# umodular_mega_shield_rev01.net
KiCad netlist of a schematic drawn in EAGLE
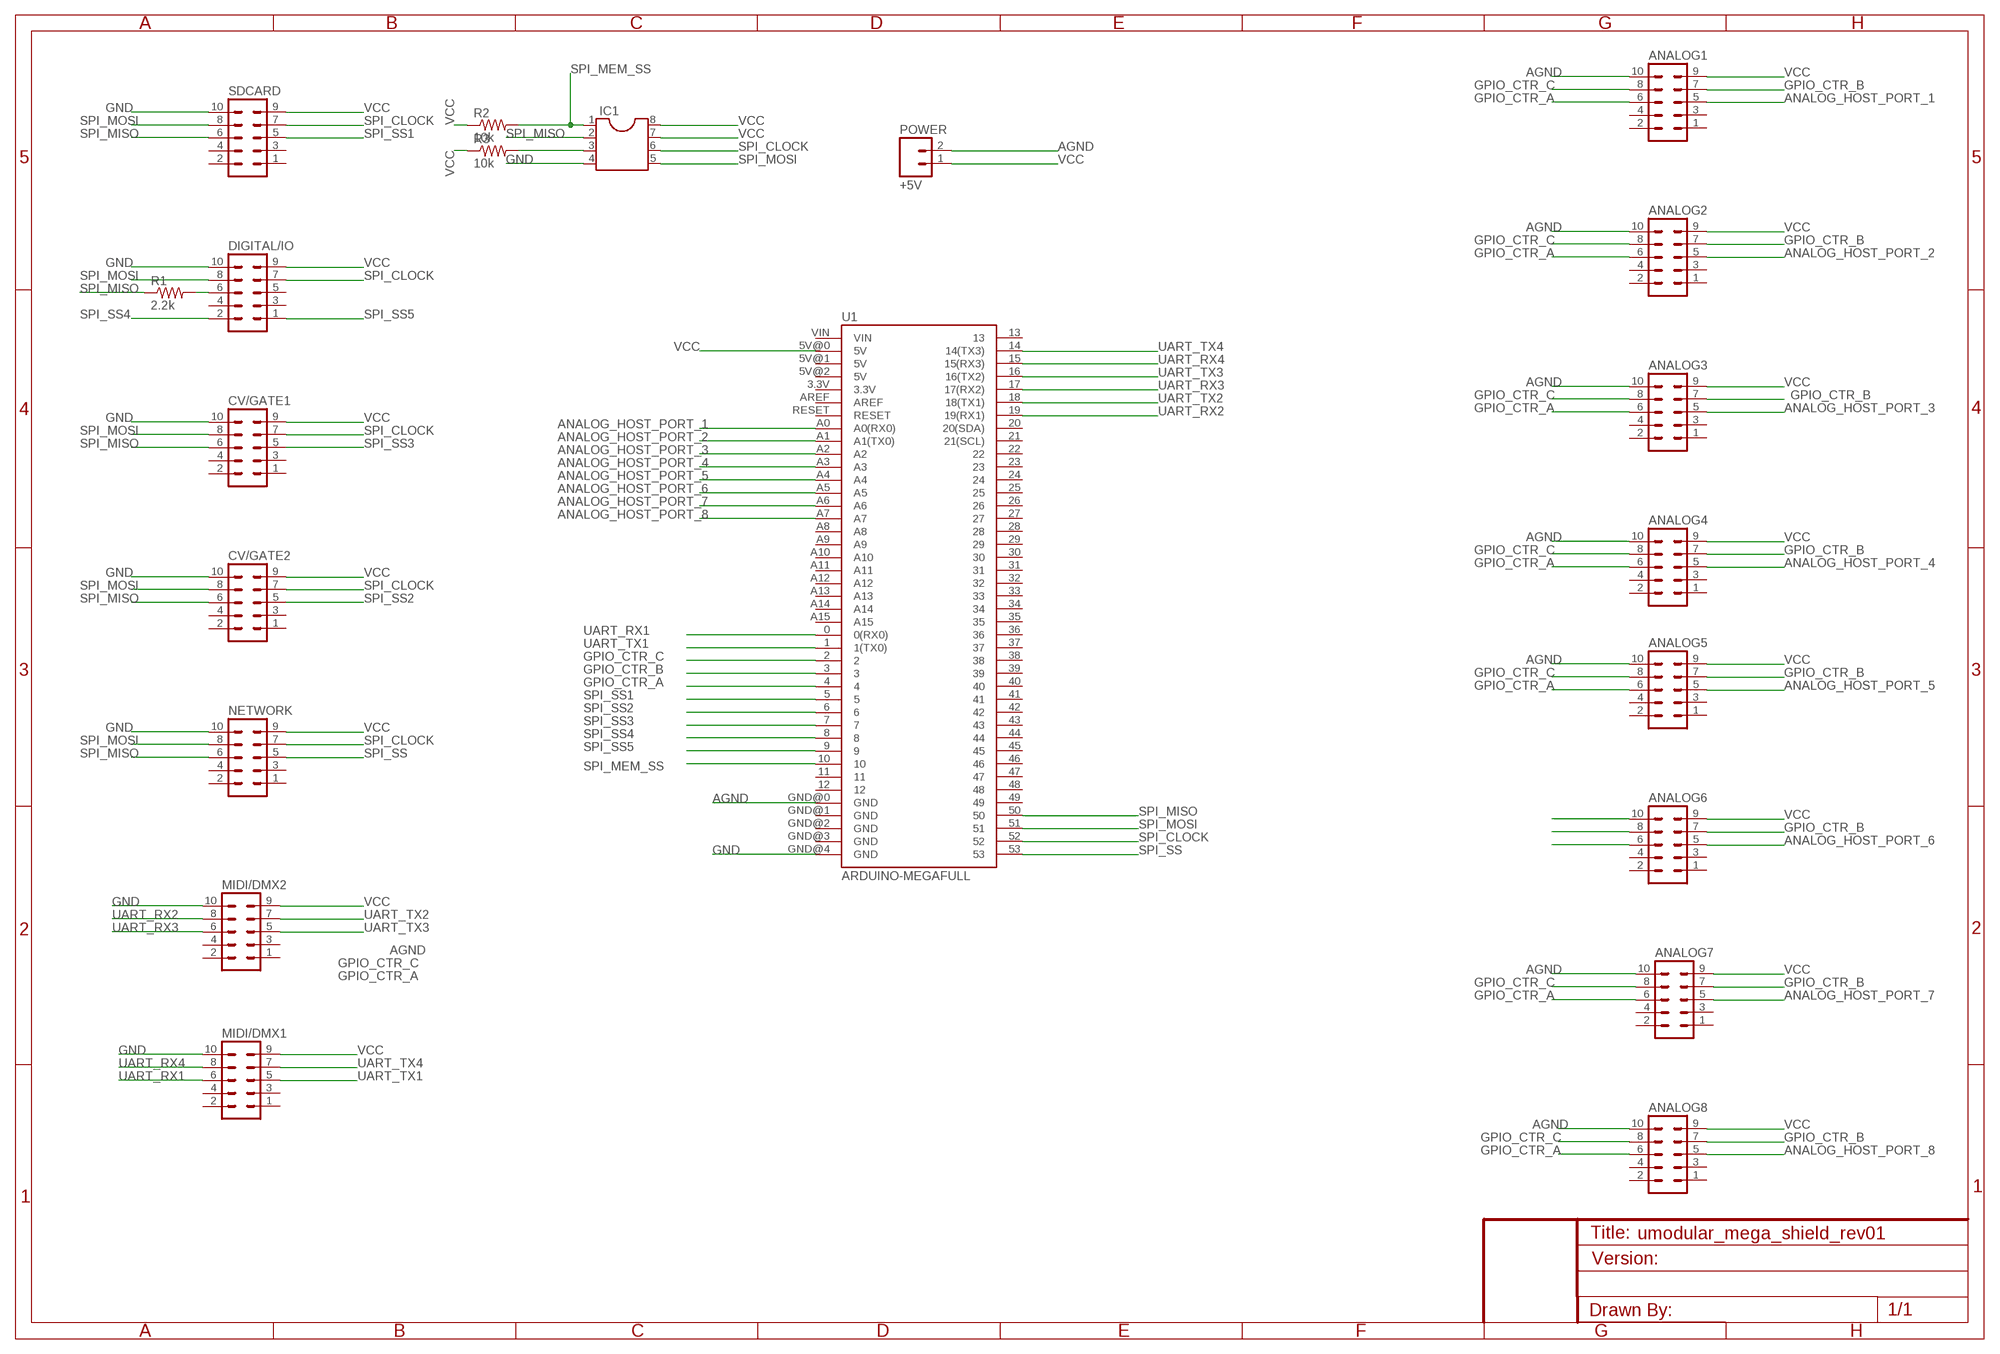
[diagram p0: schematic, sheet 1]

(export (version "E")
  (design (tool "Eeschema 10.0.6"))
  (components
    (comp (ref "ANALOG1")
      (value "MA05-2")
      (footprint "eagle-import:MA05-2")
      (libsource (lib "eagle-import") (part "MA05-2"))
    )
    (comp (ref "ANALOG2")
      (value "MA05-2")
      (footprint "eagle-import:MA05-2")
      (libsource (lib "eagle-import") (part "MA05-2"))
    )
    (comp (ref "ANALOG3")
      (value "MA05-2")
      (footprint "eagle-import:MA05-2")
      (libsource (lib "eagle-import") (part "MA05-2"))
    )
    (comp (ref "ANALOG4")
      (value "MA05-2")
      (footprint "eagle-import:MA05-2")
      (libsource (lib "eagle-import") (part "MA05-2"))
    )
    (comp (ref "ANALOG5")
      (value "MA05-2")
      (footprint "eagle-import:MA05-2")
      (libsource (lib "eagle-import") (part "MA05-2"))
    )
    (comp (ref "ANALOG6")
      (value "MA05-2")
      (footprint "eagle-import:MA05-2")
      (libsource (lib "eagle-import") (part "MA05-2"))
    )
    (comp (ref "ANALOG7")
      (value "MA05-2")
      (footprint "eagle-import:MA05-2")
      (libsource (lib "eagle-import") (part "MA05-2"))
    )
    (comp (ref "ANALOG8")
      (value "MA05-2")
      (footprint "eagle-import:MA05-2")
      (libsource (lib "eagle-import") (part "MA05-2"))
    )
    (comp (ref "CV/GATE1")
      (value "MA05-2")
      (footprint "eagle-import:MA05-2")
      (libsource (lib "eagle-import") (part "MA05-2"))
    )
    (comp (ref "CV/GATE2")
      (value "MA05-2")
      (footprint "eagle-import:MA05-2")
      (libsource (lib "eagle-import") (part "MA05-2"))
    )
    (comp (ref "DIGITAL/IO")
      (value "MA05-2")
      (footprint "eagle-import:MA05-2")
      (libsource (lib "eagle-import") (part "MA05-2"))
    )
    (comp (ref "IC1")
      (value "DIL8")
      (footprint "eagle-import:DIL08")
      (libsource (lib "eagle-import") (part "DIL8"))
    )
    (comp (ref "MIDI/DMX1")
      (value "MA05-2")
      (footprint "eagle-import:MA05-2")
      (libsource (lib "eagle-import") (part "MA05-2"))
    )
    (comp (ref "MIDI/DMX2")
      (value "MA05-2")
      (footprint "eagle-import:MA05-2")
      (libsource (lib "eagle-import") (part "MA05-2"))
    )
    (comp (ref "NETWORK")
      (value "MA05-2")
      (footprint "eagle-import:MA05-2")
      (libsource (lib "eagle-import") (part "MA05-2"))
    )
    (comp (ref "POWER")
      (value "+5V")
      (footprint "eagle-import:1X02_LOCK_LONGPADS")
      (libsource (lib "eagle-import") (part "M02LOCK_LONGPADS"))
    )
    (comp (ref "R1")
      (value "2.2k")
      (footprint "eagle-import:0204_7")
      (libsource (lib "eagle-import") (part "R-US_0204/7"))
    )
    (comp (ref "R2")
      (value "10k")
      (footprint "eagle-import:0204_7")
      (libsource (lib "eagle-import") (part "R-US_0204/7"))
    )
    (comp (ref "R3")
      (value "10k")
      (footprint "eagle-import:0204_7")
      (libsource (lib "eagle-import") (part "R-US_0204/7"))
    )
    (comp (ref "SDCARD")
      (value "MA05-2")
      (footprint "eagle-import:MA05-2")
      (libsource (lib "eagle-import") (part "MA05-2"))
    )
    (comp (ref "U1")
      (value "ARDUINO-MEGAFULL")
      (footprint "eagle-import:ARDUINO_MEGA")
      (libsource (lib "eagle-import") (part "ARDUINO-MEGAFULL"))
    )
  )
  (nets
    (net (code "1") (name "/AGND") (class "Default")
      (node (ref "ANALOG1") (pin "10") (pinfunction "10_10") (pintype "passive"))
      (node (ref "ANALOG2") (pin "10") (pinfunction "10_10") (pintype "passive"))
      (node (ref "ANALOG3") (pin "10") (pinfunction "10_10") (pintype "passive"))
      (node (ref "ANALOG4") (pin "10") (pinfunction "10_10") (pintype "passive"))
      (node (ref "ANALOG5") (pin "10") (pinfunction "10_10") (pintype "passive"))
      (node (ref "ANALOG6") (pin "10") (pinfunction "10_10") (pintype "passive"))
      (node (ref "ANALOG7") (pin "10") (pinfunction "10_10") (pintype "passive"))
      (node (ref "ANALOG8") (pin "10") (pinfunction "10_10") (pintype "passive"))
      (node (ref "POWER") (pin "2") (pinfunction "2_2") (pintype "passive"))
      (node (ref "U1") (pin "GND@0") (pinfunction "GND_GND@0") (pintype "bidirectional"))
    )
    (net (code "2") (name "/ANALOG_HOST_PORT_1") (class "Default")
      (node (ref "ANALOG1") (pin "5") (pinfunction "5_5") (pintype "passive"))
      (node (ref "U1") (pin "A0") (pinfunction "A0(RX0)_A0") (pintype "bidirectional"))
    )
    (net (code "3") (name "/ANALOG_HOST_PORT_2") (class "Default")
      (node (ref "ANALOG2") (pin "5") (pinfunction "5_5") (pintype "passive"))
      (node (ref "U1") (pin "A1") (pinfunction "A1(TX0)_A1") (pintype "bidirectional"))
    )
    (net (code "4") (name "/ANALOG_HOST_PORT_3") (class "Default")
      (node (ref "ANALOG3") (pin "5") (pinfunction "5_5") (pintype "passive"))
      (node (ref "U1") (pin "A2") (pinfunction "A2_A2") (pintype "bidirectional"))
    )
    (net (code "5") (name "/ANALOG_HOST_PORT_4") (class "Default")
      (node (ref "ANALOG4") (pin "5") (pinfunction "5_5") (pintype "passive"))
      (node (ref "U1") (pin "A3") (pinfunction "A3_A3") (pintype "bidirectional"))
    )
    (net (code "6") (name "/ANALOG_HOST_PORT_5") (class "Default")
      (node (ref "ANALOG5") (pin "5") (pinfunction "5_5") (pintype "passive"))
      (node (ref "U1") (pin "A4") (pinfunction "A4_A4") (pintype "bidirectional"))
    )
    (net (code "7") (name "/ANALOG_HOST_PORT_6") (class "Default")
      (node (ref "ANALOG6") (pin "5") (pinfunction "5_5") (pintype "passive"))
      (node (ref "U1") (pin "A5") (pinfunction "A5_A5") (pintype "bidirectional"))
    )
    (net (code "8") (name "/ANALOG_HOST_PORT_7") (class "Default")
      (node (ref "ANALOG7") (pin "5") (pinfunction "5_5") (pintype "passive"))
      (node (ref "U1") (pin "A6") (pinfunction "A6_A6") (pintype "bidirectional"))
    )
    (net (code "9") (name "/ANALOG_HOST_PORT_8") (class "Default")
      (node (ref "ANALOG8") (pin "5") (pinfunction "5_5") (pintype "passive"))
      (node (ref "U1") (pin "A7") (pinfunction "A7_A7") (pintype "bidirectional"))
    )
    (net (code "10") (name "/GND") (class "Default")
      (node (ref "CV/GATE1") (pin "10") (pinfunction "10_10") (pintype "passive"))
      (node (ref "CV/GATE2") (pin "10") (pinfunction "10_10") (pintype "passive"))
      (node (ref "DIGITAL/IO") (pin "10") (pinfunction "10_10") (pintype "passive"))
      (node (ref "IC1") (pin "4") (pinfunction "4_4") (pintype "passive"))
      (node (ref "MIDI/DMX1") (pin "10") (pinfunction "10_10") (pintype "passive"))
      (node (ref "MIDI/DMX2") (pin "10") (pinfunction "10_10") (pintype "passive"))
      (node (ref "NETWORK") (pin "10") (pinfunction "10_10") (pintype "passive"))
      (node (ref "SDCARD") (pin "10") (pinfunction "10_10") (pintype "passive"))
      (node (ref "U1") (pin "GND@4") (pinfunction "GND_GND@4") (pintype "bidirectional"))
    )
    (net (code "11") (name "/GPIO_CTR_A") (class "Default")
      (node (ref "ANALOG1") (pin "6") (pinfunction "6_6") (pintype "passive"))
      (node (ref "ANALOG2") (pin "6") (pinfunction "6_6") (pintype "passive"))
      (node (ref "ANALOG3") (pin "6") (pinfunction "6_6") (pintype "passive"))
      (node (ref "ANALOG4") (pin "6") (pinfunction "6_6") (pintype "passive"))
      (node (ref "ANALOG5") (pin "6") (pinfunction "6_6") (pintype "passive"))
      (node (ref "ANALOG6") (pin "6") (pinfunction "6_6") (pintype "passive"))
      (node (ref "ANALOG7") (pin "6") (pinfunction "6_6") (pintype "passive"))
      (node (ref "ANALOG8") (pin "6") (pinfunction "6_6") (pintype "passive"))
      (node (ref "U1") (pin "4") (pinfunction "4_4") (pintype "bidirectional"))
    )
    (net (code "12") (name "/GPIO_CTR_B") (class "Default")
      (node (ref "ANALOG1") (pin "7") (pinfunction "7_7") (pintype "passive"))
      (node (ref "ANALOG2") (pin "7") (pinfunction "7_7") (pintype "passive"))
      (node (ref "ANALOG3") (pin "7") (pinfunction "7_7") (pintype "passive"))
      (node (ref "ANALOG4") (pin "7") (pinfunction "7_7") (pintype "passive"))
      (node (ref "ANALOG5") (pin "7") (pinfunction "7_7") (pintype "passive"))
      (node (ref "ANALOG6") (pin "7") (pinfunction "7_7") (pintype "passive"))
      (node (ref "ANALOG7") (pin "7") (pinfunction "7_7") (pintype "passive"))
      (node (ref "ANALOG8") (pin "7") (pinfunction "7_7") (pintype "passive"))
      (node (ref "U1") (pin "3") (pinfunction "3_3") (pintype "bidirectional"))
    )
    (net (code "13") (name "/GPIO_CTR_C") (class "Default")
      (node (ref "ANALOG1") (pin "8") (pinfunction "8_8") (pintype "passive"))
      (node (ref "ANALOG2") (pin "8") (pinfunction "8_8") (pintype "passive"))
      (node (ref "ANALOG3") (pin "8") (pinfunction "8_8") (pintype "passive"))
      (node (ref "ANALOG4") (pin "8") (pinfunction "8_8") (pintype "passive"))
      (node (ref "ANALOG5") (pin "8") (pinfunction "8_8") (pintype "passive"))
      (node (ref "ANALOG6") (pin "8") (pinfunction "8_8") (pintype "passive"))
      (node (ref "ANALOG7") (pin "8") (pinfunction "8_8") (pintype "passive"))
      (node (ref "ANALOG8") (pin "8") (pinfunction "8_8") (pintype "passive"))
      (node (ref "U1") (pin "2") (pinfunction "2_2") (pintype "bidirectional"))
    )
    (net (code "14") (name "/SPI_CLOCK") (class "Default")
      (node (ref "CV/GATE1") (pin "7") (pinfunction "7_7") (pintype "passive"))
      (node (ref "CV/GATE2") (pin "7") (pinfunction "7_7") (pintype "passive"))
      (node (ref "DIGITAL/IO") (pin "7") (pinfunction "7_7") (pintype "passive"))
      (node (ref "IC1") (pin "6") (pinfunction "6_6") (pintype "passive"))
      (node (ref "NETWORK") (pin "7") (pinfunction "7_7") (pintype "passive"))
      (node (ref "SDCARD") (pin "7") (pinfunction "7_7") (pintype "passive"))
      (node (ref "U1") (pin "52") (pinfunction "52_52") (pintype "bidirectional"))
    )
    (net (code "15") (name "/SPI_MEM_SS") (class "Default")
      (node (ref "IC1") (pin "1") (pinfunction "1_1") (pintype "passive"))
      (node (ref "R2") (pin "2") (pinfunction "2_2") (pintype "passive"))
      (node (ref "U1") (pin "10") (pinfunction "10_10") (pintype "bidirectional"))
    )
    (net (code "16") (name "/SPI_MISO") (class "Default")
      (node (ref "CV/GATE1") (pin "6") (pinfunction "6_6") (pintype "passive"))
      (node (ref "CV/GATE2") (pin "6") (pinfunction "6_6") (pintype "passive"))
      (node (ref "IC1") (pin "2") (pinfunction "2_2") (pintype "passive"))
      (node (ref "NETWORK") (pin "6") (pinfunction "6_6") (pintype "passive"))
      (node (ref "R1") (pin "1") (pinfunction "1_1") (pintype "passive"))
      (node (ref "SDCARD") (pin "6") (pinfunction "6_6") (pintype "passive"))
      (node (ref "U1") (pin "50") (pinfunction "50_50") (pintype "bidirectional"))
    )
    (net (code "17") (name "/SPI_MOSI") (class "Default")
      (node (ref "CV/GATE1") (pin "8") (pinfunction "8_8") (pintype "passive"))
      (node (ref "CV/GATE2") (pin "8") (pinfunction "8_8") (pintype "passive"))
      (node (ref "DIGITAL/IO") (pin "8") (pinfunction "8_8") (pintype "passive"))
      (node (ref "IC1") (pin "5") (pinfunction "5_5") (pintype "passive"))
      (node (ref "NETWORK") (pin "8") (pinfunction "8_8") (pintype "passive"))
      (node (ref "SDCARD") (pin "8") (pinfunction "8_8") (pintype "passive"))
      (node (ref "U1") (pin "51") (pinfunction "51_51") (pintype "bidirectional"))
    )
    (net (code "18") (name "/SPI_SS") (class "Default")
      (node (ref "NETWORK") (pin "5") (pinfunction "5_5") (pintype "passive"))
      (node (ref "U1") (pin "53") (pinfunction "53_53") (pintype "bidirectional"))
    )
    (net (code "19") (name "/SPI_SS1") (class "Default")
      (node (ref "SDCARD") (pin "5") (pinfunction "5_5") (pintype "passive"))
      (node (ref "U1") (pin "5") (pinfunction "5_5") (pintype "bidirectional"))
    )
    (net (code "20") (name "/SPI_SS2") (class "Default")
      (node (ref "CV/GATE2") (pin "5") (pinfunction "5_5") (pintype "passive"))
      (node (ref "U1") (pin "6") (pinfunction "6_6") (pintype "bidirectional"))
    )
    (net (code "21") (name "/SPI_SS3") (class "Default")
      (node (ref "CV/GATE1") (pin "5") (pinfunction "5_5") (pintype "passive"))
      (node (ref "U1") (pin "7") (pinfunction "7_7") (pintype "bidirectional"))
    )
    (net (code "22") (name "/SPI_SS4") (class "Default")
      (node (ref "DIGITAL/IO") (pin "2") (pinfunction "2_2") (pintype "passive"))
      (node (ref "U1") (pin "8") (pinfunction "8_8") (pintype "bidirectional"))
    )
    (net (code "23") (name "/SPI_SS5") (class "Default")
      (node (ref "DIGITAL/IO") (pin "1") (pinfunction "1_1") (pintype "passive"))
      (node (ref "U1") (pin "9") (pinfunction "9_9") (pintype "bidirectional"))
    )
    (net (code "24") (name "/UART_RX1") (class "Default")
      (node (ref "MIDI/DMX1") (pin "6") (pinfunction "6_6") (pintype "passive"))
      (node (ref "U1") (pin "0") (pinfunction "0(RX0)_0") (pintype "bidirectional"))
    )
    (net (code "25") (name "/UART_RX2") (class "Default")
      (node (ref "MIDI/DMX2") (pin "8") (pinfunction "8_8") (pintype "passive"))
      (node (ref "U1") (pin "19") (pinfunction "19(RX1)_19") (pintype "bidirectional"))
    )
    (net (code "26") (name "/UART_RX3") (class "Default")
      (node (ref "MIDI/DMX2") (pin "6") (pinfunction "6_6") (pintype "passive"))
      (node (ref "U1") (pin "17") (pinfunction "17(RX2)_17") (pintype "bidirectional"))
    )
    (net (code "27") (name "/UART_RX4") (class "Default")
      (node (ref "MIDI/DMX1") (pin "8") (pinfunction "8_8") (pintype "passive"))
      (node (ref "U1") (pin "15") (pinfunction "15(RX3)_15") (pintype "bidirectional"))
    )
    (net (code "28") (name "/UART_TX1") (class "Default")
      (node (ref "MIDI/DMX1") (pin "5") (pinfunction "5_5") (pintype "passive"))
      (node (ref "U1") (pin "1") (pinfunction "1(TX0)_1") (pintype "bidirectional"))
    )
    (net (code "29") (name "/UART_TX2") (class "Default")
      (node (ref "MIDI/DMX2") (pin "7") (pinfunction "7_7") (pintype "passive"))
      (node (ref "U1") (pin "18") (pinfunction "18(TX1)_18") (pintype "bidirectional"))
    )
    (net (code "30") (name "/UART_TX3") (class "Default")
      (node (ref "MIDI/DMX2") (pin "5") (pinfunction "5_5") (pintype "passive"))
      (node (ref "U1") (pin "16") (pinfunction "16(TX2)_16") (pintype "bidirectional"))
    )
    (net (code "31") (name "/UART_TX4") (class "Default")
      (node (ref "MIDI/DMX1") (pin "7") (pinfunction "7_7") (pintype "passive"))
      (node (ref "U1") (pin "14") (pinfunction "14(TX3)_14") (pintype "bidirectional"))
    )
    (net (code "32") (name "/VCC") (class "Default")
      (node (ref "ANALOG1") (pin "9") (pinfunction "9_9") (pintype "passive"))
      (node (ref "ANALOG2") (pin "9") (pinfunction "9_9") (pintype "passive"))
      (node (ref "ANALOG3") (pin "9") (pinfunction "9_9") (pintype "passive"))
      (node (ref "ANALOG4") (pin "9") (pinfunction "9_9") (pintype "passive"))
      (node (ref "ANALOG5") (pin "9") (pinfunction "9_9") (pintype "passive"))
      (node (ref "ANALOG6") (pin "9") (pinfunction "9_9") (pintype "passive"))
      (node (ref "ANALOG7") (pin "9") (pinfunction "9_9") (pintype "passive"))
      (node (ref "ANALOG8") (pin "9") (pinfunction "9_9") (pintype "passive"))
      (node (ref "CV/GATE1") (pin "9") (pinfunction "9_9") (pintype "passive"))
      (node (ref "CV/GATE2") (pin "9") (pinfunction "9_9") (pintype "passive"))
      (node (ref "DIGITAL/IO") (pin "9") (pinfunction "9_9") (pintype "passive"))
      (node (ref "IC1") (pin "7") (pinfunction "7_7") (pintype "passive"))
      (node (ref "IC1") (pin "8") (pinfunction "8_8") (pintype "passive"))
      (node (ref "MIDI/DMX1") (pin "9") (pinfunction "9_9") (pintype "passive"))
      (node (ref "MIDI/DMX2") (pin "9") (pinfunction "9_9") (pintype "passive"))
      (node (ref "NETWORK") (pin "9") (pinfunction "9_9") (pintype "passive"))
      (node (ref "POWER") (pin "1") (pinfunction "1_1") (pintype "passive"))
      (node (ref "R2") (pin "1") (pinfunction "1_1") (pintype "passive"))
      (node (ref "R3") (pin "1") (pinfunction "1_1") (pintype "passive"))
      (node (ref "SDCARD") (pin "9") (pinfunction "9_9") (pintype "passive"))
      (node (ref "U1") (pin "5V@0") (pinfunction "5V_5V@0") (pintype "bidirectional"))
    )
    (net (code "33") (name "Net-(DIGITAL/IO-Pad6)") (class "Default")
      (node (ref "DIGITAL/IO") (pin "6") (pinfunction "6_6") (pintype "passive"))
      (node (ref "R1") (pin "2") (pinfunction "2_2") (pintype "passive"))
    )
    (net (code "34") (name "Net-(IC1-Pad3)") (class "Default")
      (node (ref "IC1") (pin "3") (pinfunction "3_3") (pintype "passive"))
      (node (ref "R3") (pin "2") (pinfunction "2_2") (pintype "passive"))
    )
    (net (code "35") (name "unconnected-(ANALOG1-Pad1)") (class "Default")
      (node (ref "ANALOG1") (pin "1") (pinfunction "1_1") (pintype "passive"))
    )
    (net (code "36") (name "unconnected-(ANALOG1-Pad2)") (class "Default")
      (node (ref "ANALOG1") (pin "2") (pinfunction "2_2") (pintype "passive"))
    )
    (net (code "37") (name "unconnected-(ANALOG1-Pad3)") (class "Default")
      (node (ref "ANALOG1") (pin "3") (pinfunction "3_3") (pintype "passive"))
    )
    (net (code "38") (name "unconnected-(ANALOG1-Pad4)") (class "Default")
      (node (ref "ANALOG1") (pin "4") (pinfunction "4_4") (pintype "passive"))
    )
    (net (code "39") (name "unconnected-(ANALOG2-Pad1)") (class "Default")
      (node (ref "ANALOG2") (pin "1") (pinfunction "1_1") (pintype "passive"))
    )
    (net (code "40") (name "unconnected-(ANALOG2-Pad2)") (class "Default")
      (node (ref "ANALOG2") (pin "2") (pinfunction "2_2") (pintype "passive"))
    )
    (net (code "41") (name "unconnected-(ANALOG2-Pad3)") (class "Default")
      (node (ref "ANALOG2") (pin "3") (pinfunction "3_3") (pintype "passive"))
    )
    (net (code "42") (name "unconnected-(ANALOG2-Pad4)") (class "Default")
      (node (ref "ANALOG2") (pin "4") (pinfunction "4_4") (pintype "passive"))
    )
    (net (code "43") (name "unconnected-(ANALOG3-Pad1)") (class "Default")
      (node (ref "ANALOG3") (pin "1") (pinfunction "1_1") (pintype "passive"))
    )
    (net (code "44") (name "unconnected-(ANALOG3-Pad2)") (class "Default")
      (node (ref "ANALOG3") (pin "2") (pinfunction "2_2") (pintype "passive"))
    )
    (net (code "45") (name "unconnected-(ANALOG3-Pad3)") (class "Default")
      (node (ref "ANALOG3") (pin "3") (pinfunction "3_3") (pintype "passive"))
    )
    (net (code "46") (name "unconnected-(ANALOG3-Pad4)") (class "Default")
      (node (ref "ANALOG3") (pin "4") (pinfunction "4_4") (pintype "passive"))
    )
    (net (code "47") (name "unconnected-(ANALOG4-Pad1)") (class "Default")
      (node (ref "ANALOG4") (pin "1") (pinfunction "1_1") (pintype "passive"))
    )
    (net (code "48") (name "unconnected-(ANALOG4-Pad2)") (class "Default")
      (node (ref "ANALOG4") (pin "2") (pinfunction "2_2") (pintype "passive"))
    )
    (net (code "49") (name "unconnected-(ANALOG4-Pad3)") (class "Default")
      (node (ref "ANALOG4") (pin "3") (pinfunction "3_3") (pintype "passive"))
    )
    (net (code "50") (name "unconnected-(ANALOG4-Pad4)") (class "Default")
      (node (ref "ANALOG4") (pin "4") (pinfunction "4_4") (pintype "passive"))
    )
    (net (code "51") (name "unconnected-(ANALOG5-Pad1)") (class "Default")
      (node (ref "ANALOG5") (pin "1") (pinfunction "1_1") (pintype "passive"))
    )
    (net (code "52") (name "unconnected-(ANALOG5-Pad2)") (class "Default")
      (node (ref "ANALOG5") (pin "2") (pinfunction "2_2") (pintype "passive"))
    )
    (net (code "53") (name "unconnected-(ANALOG5-Pad3)") (class "Default")
      (node (ref "ANALOG5") (pin "3") (pinfunction "3_3") (pintype "passive"))
    )
    (net (code "54") (name "unconnected-(ANALOG5-Pad4)") (class "Default")
      (node (ref "ANALOG5") (pin "4") (pinfunction "4_4") (pintype "passive"))
    )
    (net (code "55") (name "unconnected-(ANALOG6-Pad1)") (class "Default")
      (node (ref "ANALOG6") (pin "1") (pinfunction "1_1") (pintype "passive"))
    )
    (net (code "56") (name "unconnected-(ANALOG6-Pad2)") (class "Default")
      (node (ref "ANALOG6") (pin "2") (pinfunction "2_2") (pintype "passive"))
    )
    (net (code "57") (name "unconnected-(ANALOG6-Pad3)") (class "Default")
      (node (ref "ANALOG6") (pin "3") (pinfunction "3_3") (pintype "passive"))
    )
    (net (code "58") (name "unconnected-(ANALOG6-Pad4)") (class "Default")
      (node (ref "ANALOG6") (pin "4") (pinfunction "4_4") (pintype "passive"))
    )
    (net (code "59") (name "unconnected-(ANALOG7-Pad1)") (class "Default")
      (node (ref "ANALOG7") (pin "1") (pinfunction "1_1") (pintype "passive"))
    )
    (net (code "60") (name "unconnected-(ANALOG7-Pad2)") (class "Default")
      (node (ref "ANALOG7") (pin "2") (pinfunction "2_2") (pintype "passive"))
    )
    (net (code "61") (name "unconnected-(ANALOG7-Pad3)") (class "Default")
      (node (ref "ANALOG7") (pin "3") (pinfunction "3_3") (pintype "passive"))
    )
    (net (code "62") (name "unconnected-(ANALOG7-Pad4)") (class "Default")
      (node (ref "ANALOG7") (pin "4") (pinfunction "4_4") (pintype "passive"))
    )
    (net (code "63") (name "unconnected-(ANALOG8-Pad1)") (class "Default")
      (node (ref "ANALOG8") (pin "1") (pinfunction "1_1") (pintype "passive"))
    )
    (net (code "64") (name "unconnected-(ANALOG8-Pad2)") (class "Default")
      (node (ref "ANALOG8") (pin "2") (pinfunction "2_2") (pintype "passive"))
    )
    (net (code "65") (name "unconnected-(ANALOG8-Pad3)") (class "Default")
      (node (ref "ANALOG8") (pin "3") (pinfunction "3_3") (pintype "passive"))
    )
    (net (code "66") (name "unconnected-(ANALOG8-Pad4)") (class "Default")
      (node (ref "ANALOG8") (pin "4") (pinfunction "4_4") (pintype "passive"))
    )
    (net (code "67") (name "unconnected-(CV/GATE1-Pad1)") (class "Default")
      (node (ref "CV/GATE1") (pin "1") (pinfunction "1_1") (pintype "passive"))
    )
    (net (code "68") (name "unconnected-(CV/GATE1-Pad2)") (class "Default")
      (node (ref "CV/GATE1") (pin "2") (pinfunction "2_2") (pintype "passive"))
    )
    (net (code "69") (name "unconnected-(CV/GATE1-Pad3)") (class "Default")
      (node (ref "CV/GATE1") (pin "3") (pinfunction "3_3") (pintype "passive"))
    )
    (net (code "70") (name "unconnected-(CV/GATE1-Pad4)") (class "Default")
      (node (ref "CV/GATE1") (pin "4") (pinfunction "4_4") (pintype "passive"))
    )
    (net (code "71") (name "unconnected-(CV/GATE2-Pad1)") (class "Default")
      (node (ref "CV/GATE2") (pin "1") (pinfunction "1_1") (pintype "passive"))
    )
    (net (code "72") (name "unconnected-(CV/GATE2-Pad2)") (class "Default")
      (node (ref "CV/GATE2") (pin "2") (pinfunction "2_2") (pintype "passive"))
    )
    (net (code "73") (name "unconnected-(CV/GATE2-Pad3)") (class "Default")
      (node (ref "CV/GATE2") (pin "3") (pinfunction "3_3") (pintype "passive"))
    )
    (net (code "74") (name "unconnected-(CV/GATE2-Pad4)") (class "Default")
      (node (ref "CV/GATE2") (pin "4") (pinfunction "4_4") (pintype "passive"))
    )
    (net (code "75") (name "unconnected-(DIGITAL/IO-Pad3)") (class "Default")
      (node (ref "DIGITAL/IO") (pin "3") (pinfunction "3_3") (pintype "passive"))
    )
    (net (code "76") (name "unconnected-(DIGITAL/IO-Pad4)") (class "Default")
      (node (ref "DIGITAL/IO") (pin "4") (pinfunction "4_4") (pintype "passive"))
    )
    (net (code "77") (name "unconnected-(DIGITAL/IO-Pad5)") (class "Default")
      (node (ref "DIGITAL/IO") (pin "5") (pinfunction "5_5") (pintype "passive"))
    )
    (net (code "78") (name "unconnected-(MIDI/DMX1-Pad1)") (class "Default")
      (node (ref "MIDI/DMX1") (pin "1") (pinfunction "1_1") (pintype "passive"))
    )
    (net (code "79") (name "unconnected-(MIDI/DMX1-Pad2)") (class "Default")
      (node (ref "MIDI/DMX1") (pin "2") (pinfunction "2_2") (pintype "passive"))
    )
    (net (code "80") (name "unconnected-(MIDI/DMX1-Pad3)") (class "Default")
      (node (ref "MIDI/DMX1") (pin "3") (pinfunction "3_3") (pintype "passive"))
    )
    (net (code "81") (name "unconnected-(MIDI/DMX1-Pad4)") (class "Default")
      (node (ref "MIDI/DMX1") (pin "4") (pinfunction "4_4") (pintype "passive"))
    )
    (net (code "82") (name "unconnected-(MIDI/DMX2-Pad1)") (class "Default")
      (node (ref "MIDI/DMX2") (pin "1") (pinfunction "1_1") (pintype "passive"))
    )
    (net (code "83") (name "unconnected-(MIDI/DMX2-Pad2)") (class "Default")
      (node (ref "MIDI/DMX2") (pin "2") (pinfunction "2_2") (pintype "passive"))
    )
    (net (code "84") (name "unconnected-(MIDI/DMX2-Pad3)") (class "Default")
      (node (ref "MIDI/DMX2") (pin "3") (pinfunction "3_3") (pintype "passive"))
    )
    (net (code "85") (name "unconnected-(MIDI/DMX2-Pad4)") (class "Default")
      (node (ref "MIDI/DMX2") (pin "4") (pinfunction "4_4") (pintype "passive"))
    )
    (net (code "86") (name "unconnected-(NETWORK-Pad1)") (class "Default")
      (node (ref "NETWORK") (pin "1") (pinfunction "1_1") (pintype "passive"))
    )
    (net (code "87") (name "unconnected-(NETWORK-Pad2)") (class "Default")
      (node (ref "NETWORK") (pin "2") (pinfunction "2_2") (pintype "passive"))
    )
    (net (code "88") (name "unconnected-(NETWORK-Pad3)") (class "Default")
      (node (ref "NETWORK") (pin "3") (pinfunction "3_3") (pintype "passive"))
    )
    (net (code "89") (name "unconnected-(NETWORK-Pad4)") (class "Default")
      (node (ref "NETWORK") (pin "4") (pinfunction "4_4") (pintype "passive"))
    )
    (net (code "90") (name "unconnected-(SDCARD-Pad1)") (class "Default")
      (node (ref "SDCARD") (pin "1") (pinfunction "1_1") (pintype "passive"))
    )
    (net (code "91") (name "unconnected-(SDCARD-Pad2)") (class "Default")
      (node (ref "SDCARD") (pin "2") (pinfunction "2_2") (pintype "passive"))
    )
    (net (code "92") (name "unconnected-(SDCARD-Pad3)") (class "Default")
      (node (ref "SDCARD") (pin "3") (pinfunction "3_3") (pintype "passive"))
    )
    (net (code "93") (name "unconnected-(SDCARD-Pad4)") (class "Default")
      (node (ref "SDCARD") (pin "4") (pinfunction "4_4") (pintype "passive"))
    )
    (net (code "94") (name "unconnected-(U1-5V-Pad5V@1)") (class "Default")
      (node (ref "U1") (pin "5V@1") (pinfunction "5V_5V@1") (pintype "bidirectional"))
    )
    (net (code "95") (name "unconnected-(U1-5V-Pad5V@2)") (class "Default")
      (node (ref "U1") (pin "5V@2") (pinfunction "5V_5V@2") (pintype "bidirectional"))
    )
    (net (code "96") (name "unconnected-(U1-20(SDA)-Pad20)") (class "Default")
      (node (ref "U1") (pin "20") (pinfunction "20(SDA)_20") (pintype "bidirectional"))
    )
    (net (code "97") (name "unconnected-(U1-21(SCL)-Pad21)") (class "Default")
      (node (ref "U1") (pin "21") (pinfunction "21(SCL)_21") (pintype "bidirectional"))
    )
    (net (code "98") (name "unconnected-(U1-GND-PadGND@1)") (class "Default")
      (node (ref "U1") (pin "GND@1") (pinfunction "GND_GND@1") (pintype "bidirectional"))
    )
    (net (code "99") (name "unconnected-(U1-GND-PadGND@2)") (class "Default")
      (node (ref "U1") (pin "GND@2") (pinfunction "GND_GND@2") (pintype "bidirectional"))
    )
    (net (code "100") (name "unconnected-(U1-GND-PadGND@3)") (class "Default")
      (node (ref "U1") (pin "GND@3") (pinfunction "GND_GND@3") (pintype "bidirectional"))
    )
    (net (code "101") (name "unconnected-(U1-Pad3.3V)") (class "Default")
      (node (ref "U1") (pin "3.3V") (pinfunction "3.3V_3.3V") (pintype "bidirectional"))
    )
    (net (code "102") (name "unconnected-(U1-Pad11)") (class "Default")
      (node (ref "U1") (pin "11") (pinfunction "11_11") (pintype "bidirectional"))
    )
    (net (code "103") (name "unconnected-(U1-Pad12)") (class "Default")
      (node (ref "U1") (pin "12") (pinfunction "12_12") (pintype "bidirectional"))
    )
    (net (code "104") (name "unconnected-(U1-Pad13)") (class "Default")
      (node (ref "U1") (pin "13") (pinfunction "13_13") (pintype "bidirectional"))
    )
    (net (code "105") (name "unconnected-(U1-Pad22)") (class "Default")
      (node (ref "U1") (pin "22") (pinfunction "22_22") (pintype "bidirectional"))
    )
    (net (code "106") (name "unconnected-(U1-Pad23)") (class "Default")
      (node (ref "U1") (pin "23") (pinfunction "23_23") (pintype "bidirectional"))
    )
    (net (code "107") (name "unconnected-(U1-Pad24)") (class "Default")
      (node (ref "U1") (pin "24") (pinfunction "24_24") (pintype "bidirectional"))
    )
    (net (code "108") (name "unconnected-(U1-Pad25)") (class "Default")
      (node (ref "U1") (pin "25") (pinfunction "25_25") (pintype "bidirectional"))
    )
    (net (code "109") (name "unconnected-(U1-Pad26)") (class "Default")
      (node (ref "U1") (pin "26") (pinfunction "26_26") (pintype "bidirectional"))
    )
    (net (code "110") (name "unconnected-(U1-Pad27)") (class "Default")
      (node (ref "U1") (pin "27") (pinfunction "27_27") (pintype "bidirectional"))
    )
    (net (code "111") (name "unconnected-(U1-Pad28)") (class "Default")
      (node (ref "U1") (pin "28") (pinfunction "28_28") (pintype "bidirectional"))
    )
    (net (code "112") (name "unconnected-(U1-Pad29)") (class "Default")
      (node (ref "U1") (pin "29") (pinfunction "29_29") (pintype "bidirectional"))
    )
    (net (code "113") (name "unconnected-(U1-Pad30)") (class "Default")
      (node (ref "U1") (pin "30") (pinfunction "30_30") (pintype "bidirectional"))
    )
    (net (code "114") (name "unconnected-(U1-Pad31)") (class "Default")
      (node (ref "U1") (pin "31") (pinfunction "31_31") (pintype "bidirectional"))
    )
    (net (code "115") (name "unconnected-(U1-Pad32)") (class "Default")
      (node (ref "U1") (pin "32") (pinfunction "32_32") (pintype "bidirectional"))
    )
    (net (code "116") (name "unconnected-(U1-Pad33)") (class "Default")
      (node (ref "U1") (pin "33") (pinfunction "33_33") (pintype "bidirectional"))
    )
    (net (code "117") (name "unconnected-(U1-Pad34)") (class "Default")
      (node (ref "U1") (pin "34") (pinfunction "34_34") (pintype "bidirectional"))
    )
    (net (code "118") (name "unconnected-(U1-Pad35)") (class "Default")
      (node (ref "U1") (pin "35") (pinfunction "35_35") (pintype "bidirectional"))
    )
    (net (code "119") (name "unconnected-(U1-Pad36)") (class "Default")
      (node (ref "U1") (pin "36") (pinfunction "36_36") (pintype "bidirectional"))
    )
    (net (code "120") (name "unconnected-(U1-Pad37)") (class "Default")
      (node (ref "U1") (pin "37") (pinfunction "37_37") (pintype "bidirectional"))
    )
    (net (code "121") (name "unconnected-(U1-Pad38)") (class "Default")
      (node (ref "U1") (pin "38") (pinfunction "38_38") (pintype "bidirectional"))
    )
    (net (code "122") (name "unconnected-(U1-Pad39)") (class "Default")
      (node (ref "U1") (pin "39") (pinfunction "39_39") (pintype "bidirectional"))
    )
    (net (code "123") (name "unconnected-(U1-Pad40)") (class "Default")
      (node (ref "U1") (pin "40") (pinfunction "40_40") (pintype "bidirectional"))
    )
    (net (code "124") (name "unconnected-(U1-Pad41)") (class "Default")
      (node (ref "U1") (pin "41") (pinfunction "41_41") (pintype "bidirectional"))
    )
    (net (code "125") (name "unconnected-(U1-Pad42)") (class "Default")
      (node (ref "U1") (pin "42") (pinfunction "42_42") (pintype "bidirectional"))
    )
    (net (code "126") (name "unconnected-(U1-Pad43)") (class "Default")
      (node (ref "U1") (pin "43") (pinfunction "43_43") (pintype "bidirectional"))
    )
    (net (code "127") (name "unconnected-(U1-Pad44)") (class "Default")
      (node (ref "U1") (pin "44") (pinfunction "44_44") (pintype "bidirectional"))
    )
    (net (code "128") (name "unconnected-(U1-Pad45)") (class "Default")
      (node (ref "U1") (pin "45") (pinfunction "45_45") (pintype "bidirectional"))
    )
    (net (code "129") (name "unconnected-(U1-Pad46)") (class "Default")
      (node (ref "U1") (pin "46") (pinfunction "46_46") (pintype "bidirectional"))
    )
    (net (code "130") (name "unconnected-(U1-Pad47)") (class "Default")
      (node (ref "U1") (pin "47") (pinfunction "47_47") (pintype "bidirectional"))
    )
    (net (code "131") (name "unconnected-(U1-Pad48)") (class "Default")
      (node (ref "U1") (pin "48") (pinfunction "48_48") (pintype "bidirectional"))
    )
    (net (code "132") (name "unconnected-(U1-Pad49)") (class "Default")
      (node (ref "U1") (pin "49") (pinfunction "49_49") (pintype "bidirectional"))
    )
    (net (code "133") (name "unconnected-(U1-PadA8)") (class "Default")
      (node (ref "U1") (pin "A8") (pinfunction "A8_A8") (pintype "bidirectional"))
    )
    (net (code "134") (name "unconnected-(U1-PadA9)") (class "Default")
      (node (ref "U1") (pin "A9") (pinfunction "A9_A9") (pintype "bidirectional"))
    )
    (net (code "135") (name "unconnected-(U1-PadA10)") (class "Default")
      (node (ref "U1") (pin "A10") (pinfunction "A10_A10") (pintype "bidirectional"))
    )
    (net (code "136") (name "unconnected-(U1-PadA11)") (class "Default")
      (node (ref "U1") (pin "A11") (pinfunction "A11_A11") (pintype "bidirectional"))
    )
    (net (code "137") (name "unconnected-(U1-PadA12)") (class "Default")
      (node (ref "U1") (pin "A12") (pinfunction "A12_A12") (pintype "bidirectional"))
    )
    (net (code "138") (name "unconnected-(U1-PadA13)") (class "Default")
      (node (ref "U1") (pin "A13") (pinfunction "A13_A13") (pintype "bidirectional"))
    )
    (net (code "139") (name "unconnected-(U1-PadA14)") (class "Default")
      (node (ref "U1") (pin "A14") (pinfunction "A14_A14") (pintype "bidirectional"))
    )
    (net (code "140") (name "unconnected-(U1-PadA15)") (class "Default")
      (node (ref "U1") (pin "A15") (pinfunction "A15_A15") (pintype "bidirectional"))
    )
    (net (code "141") (name "unconnected-(U1-PadAREF)") (class "Default")
      (node (ref "U1") (pin "AREF") (pinfunction "AREF_AREF") (pintype "bidirectional"))
    )
    (net (code "142") (name "unconnected-(U1-PadRESET)") (class "Default")
      (node (ref "U1") (pin "RESET") (pinfunction "RESET_RESET") (pintype "bidirectional"))
    )
    (net (code "143") (name "unconnected-(U1-PadVIN)") (class "Default")
      (node (ref "U1") (pin "VIN") (pinfunction "VIN_VIN") (pintype "bidirectional"))
    )
  )
)
